# ADuCDn.net
KiCad netlist of a schematic drawn in Altium Designer
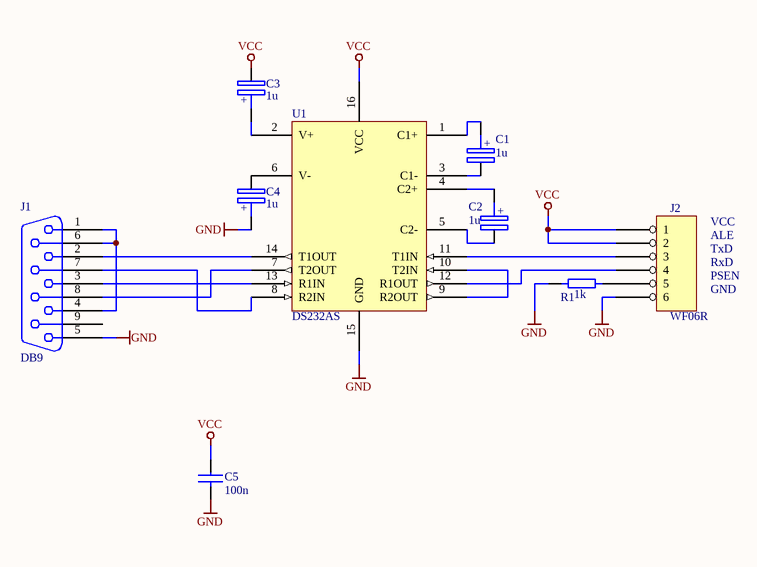
[diagram p0: ADuCDn.SchDoc]

(export (version "E")
  (design (tool "Eeschema 10.0.6"))
  (components
    (comp (ref "C1") (value "1u") (footprint "CEL1210") (libsource (lib "*") (part "CEL1210")))
    (comp (ref "C2") (value "1u") (footprint "CEL1210") (libsource (lib "*") (part "CEL1210")))
    (comp (ref "C3") (value "1u") (footprint "CEL1210") (libsource (lib "*") (part "CEL1210")))
    (comp (ref "C4") (value "1u") (footprint "CEL1210") (libsource (lib "*") (part "CEL1210")))
    (comp (ref "C5") (value "100n") (footprint "1206") (libsource (lib "*") (part "C1206")))
    (comp (ref "J1") (value "DB9") (footprint "DB9SL") (libsource (lib "*") (part "CONNECTOR DB9")))
    (comp (ref "J2") (value "WF06R") (footprint "WF06R") (libsource (lib "*") (part "HEADER 6")))
    (comp (ref "R1") (value "1k") (footprint "1206") (libsource (lib "*") (part "R")))
    (comp (ref "U1") (value "DS232AS") (footprint "16SOIC150") (libsource (lib "*") (part "MAX232 1")))
  )
  (nets
    (net (code "1") (name "GND") (class "Default")
      (node (ref "C4") (pin "2") (pinfunction "2_2") (pintype "passive"))
      (node (ref "C5") (pin "2") (pinfunction "2_2") (pintype "passive"))
      (node (ref "J1") (pin "5") (pinfunction "5_5") (pintype "passive"))
      (node (ref "J2") (pin "6") (pinfunction "6_6") (pintype "passive"))
      (node (ref "R1") (pin "1") (pinfunction "1_1") (pintype "passive"))
      (node (ref "U1") (pin "15") (pinfunction "GND_15") (pintype "power_in"))
    )
    (net (code "2") (name "Net-(J1-Pad1)") (class "Default")
      (node (ref "J1") (pin "1") (pinfunction "1_1") (pintype "passive"))
      (node (ref "J1") (pin "4") (pinfunction "4_4") (pintype "passive"))
      (node (ref "J1") (pin "6") (pinfunction "6_6") (pintype "passive"))
    )
    (net (code "3") (name "Net-(J2-Pad5)") (class "Default")
      (node (ref "J2") (pin "5") (pinfunction "5_5") (pintype "passive"))
      (node (ref "R1") (pin "2") (pinfunction "2_2") (pintype "passive"))
    )
    (net (code "4") (name "Net-(U1-C1+)") (class "Default")
      (node (ref "C1") (pin "2") (pinfunction "2_2") (pintype "passive"))
      (node (ref "U1") (pin "1") (pinfunction "C1+_1") (pintype "passive"))
    )
    (net (code "5") (name "Net-(U1-C1-)") (class "Default")
      (node (ref "C1") (pin "1") (pinfunction "1_1") (pintype "passive"))
      (node (ref "U1") (pin "3") (pinfunction "C1-_3") (pintype "passive"))
    )
    (net (code "6") (name "Net-(U1-C2+)") (class "Default")
      (node (ref "C2") (pin "2") (pinfunction "2_2") (pintype "passive"))
      (node (ref "U1") (pin "4") (pinfunction "C2+_4") (pintype "passive"))
    )
    (net (code "7") (name "Net-(U1-C2-)") (class "Default")
      (node (ref "C2") (pin "1") (pinfunction "1_1") (pintype "passive"))
      (node (ref "U1") (pin "5") (pinfunction "C2-_5") (pintype "passive"))
    )
    (net (code "8") (name "Net-(U1-R1IN)") (class "Default")
      (node (ref "J1") (pin "3") (pinfunction "3_3") (pintype "passive"))
      (node (ref "U1") (pin "13") (pinfunction "R1IN_13") (pintype "input"))
    )
    (net (code "9") (name "Net-(U1-R1OUT)") (class "Default")
      (node (ref "J2") (pin "4") (pinfunction "4_4") (pintype "passive"))
      (node (ref "U1") (pin "12") (pinfunction "R1OUT_12") (pintype "output"))
    )
    (net (code "10") (name "Net-(U1-R2IN)") (class "Default")
      (node (ref "J1") (pin "7") (pinfunction "7_7") (pintype "passive"))
      (node (ref "U1") (pin "8") (pinfunction "R2IN_8") (pintype "input"))
    )
    (net (code "11") (name "Net-(U1-R2OUT)") (class "Default")
      (node (ref "U1") (pin "10") (pinfunction "T2IN_10") (pintype "input"))
      (node (ref "U1") (pin "9") (pinfunction "R2OUT_9") (pintype "output"))
    )
    (net (code "12") (name "Net-(U1-T1IN)") (class "Default")
      (node (ref "J2") (pin "3") (pinfunction "3_3") (pintype "passive"))
      (node (ref "U1") (pin "11") (pinfunction "T1IN_11") (pintype "input"))
    )
    (net (code "13") (name "Net-(U1-T1OUT)") (class "Default")
      (node (ref "J1") (pin "2") (pinfunction "2_2") (pintype "passive"))
      (node (ref "U1") (pin "14") (pinfunction "T1OUT_14") (pintype "output"))
    )
    (net (code "14") (name "Net-(U1-T2OUT)") (class "Default")
      (node (ref "J1") (pin "8") (pinfunction "8_8") (pintype "passive"))
      (node (ref "U1") (pin "7") (pinfunction "T2OUT_7") (pintype "output"))
    )
    (net (code "15") (name "Net-(U1-V+)") (class "Default")
      (node (ref "C3") (pin "2") (pinfunction "2_2") (pintype "passive"))
      (node (ref "U1") (pin "2") (pinfunction "V+_2") (pintype "passive"))
    )
    (net (code "16") (name "Net-(U1-V-)") (class "Default")
      (node (ref "C4") (pin "1") (pinfunction "1_1") (pintype "passive"))
      (node (ref "U1") (pin "6") (pinfunction "V-_6") (pintype "passive"))
    )
    (net (code "17") (name "VCC") (class "Default")
      (node (ref "C3") (pin "1") (pinfunction "1_1") (pintype "passive"))
      (node (ref "C5") (pin "1") (pinfunction "1_1") (pintype "passive"))
      (node (ref "J2") (pin "1") (pinfunction "1_1") (pintype "passive"))
      (node (ref "J2") (pin "2") (pinfunction "2_2") (pintype "passive"))
      (node (ref "U1") (pin "16") (pinfunction "VCC_16") (pintype "power_in"))
    )
    (net (code "18") (name "unconnected-(J1-Pad9)") (class "Default")
      (node (ref "J1") (pin "9") (pinfunction "9_9") (pintype "passive"))
    )
  )
)
